# ring_modulator.net
KiCad netlist of a schematic drawn in EAGLE
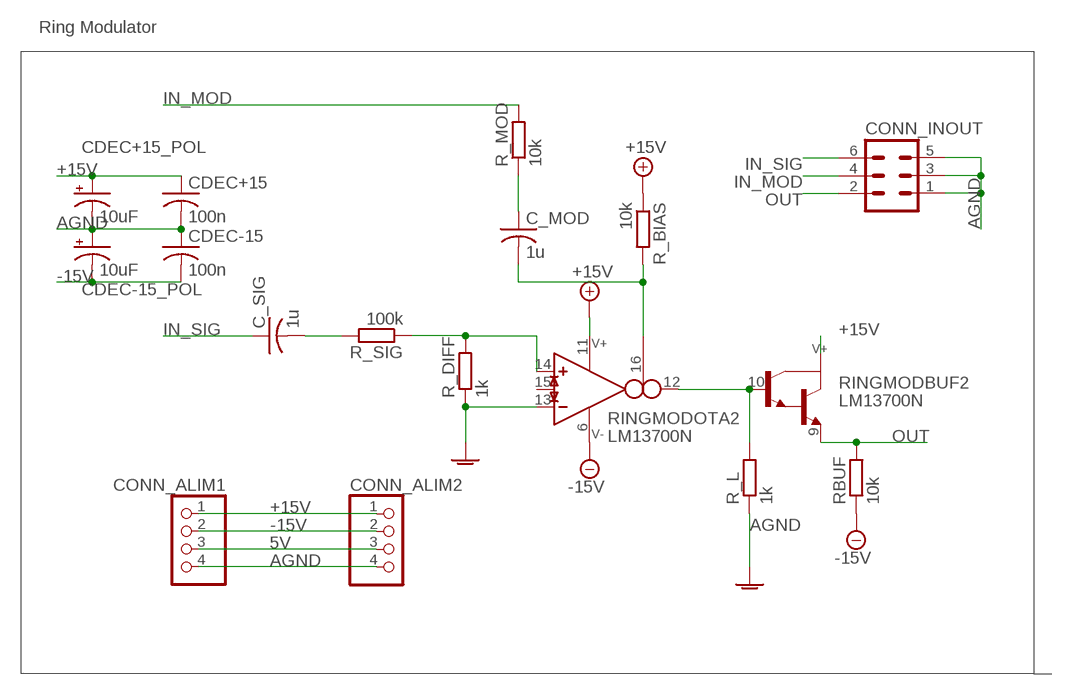
[diagram p0: schematic, sheet 1]

(export (version "E")
  (design (tool "Eeschema 10.0.6"))
  (components
    (comp (ref "CDEC+15")
      (value "100n")
      (footprint "eagle-import:C050-024X044")
      (libsource (lib "eagle-import") (part "C-US050-024X044"))
    )
    (comp (ref "CDEC+15_POL")
      (value "10uF")
      (footprint "eagle-import:CPOL-RADIAL-2.5MM-5MM-KIT")
      (libsource (lib "eagle-import") (part "10UF-POLAR-RADIAL-2.5MM-KIT-25V-20%"))
    )
    (comp (ref "CDEC-15")
      (value "100n")
      (footprint "eagle-import:C050-024X044")
      (libsource (lib "eagle-import") (part "C-US050-024X044"))
    )
    (comp (ref "CDEC-15_POL")
      (value "10uF")
      (footprint "eagle-import:CPOL-RADIAL-2.5MM-5MM-KIT")
      (libsource (lib "eagle-import") (part "10UF-POLAR-RADIAL-2.5MM-KIT-25V-20%"))
    )
    (comp (ref "CONN_ALIM1")
      (value "PINHD-1X4")
      (footprint "eagle-import:1X04")
      (libsource (lib "eagle-import") (part "PINHD-1X4"))
    )
    (comp (ref "CONN_ALIM2")
      (value "PINHD-1X4")
      (footprint "eagle-import:1X04")
      (libsource (lib "eagle-import") (part "PINHD-1X4"))
    )
    (comp (ref "CONN_INOUT")
      (value "MA03-2")
      (footprint "eagle-import:MA03-2")
      (libsource (lib "eagle-import") (part "MA03-2"))
    )
    (comp (ref "C_MOD")
      (value "1u")
      (footprint "eagle-import:C050-024X044")
      (libsource (lib "eagle-import") (part "C-US050-024X044"))
    )
    (comp (ref "C_SIG")
      (value "1u")
      (footprint "eagle-import:C050-024X044")
      (libsource (lib "eagle-import") (part "C-US050-024X044"))
    )
    (comp (ref "RBUF")
      (value "10k")
      (footprint "eagle-import:0204_7")
      (libsource (lib "eagle-import") (part "R-EU_0204/7"))
    )
    (comp (ref "RINGMOD")
      (value "LM13700N")
      (footprint "eagle-import:DIL16")
      (libsource (lib "eagle-import") (part "LM13700N"))
    )
    (comp (ref "R_BIAS")
      (value "10k")
      (footprint "eagle-import:0204_7")
      (libsource (lib "eagle-import") (part "R-EU_0204/7"))
    )
    (comp (ref "R_DIFF")
      (value "1k")
      (footprint "eagle-import:0204_7")
      (libsource (lib "eagle-import") (part "R-EU_0204/7"))
    )
    (comp (ref "R_L")
      (value "1k")
      (footprint "eagle-import:0204_7")
      (libsource (lib "eagle-import") (part "R-EU_0204/7"))
    )
    (comp (ref "R_MOD")
      (value "10k")
      (footprint "eagle-import:0204_7")
      (libsource (lib "eagle-import") (part "R-EU_0204/7"))
    )
    (comp (ref "R_SIG")
      (value "100k")
      (footprint "eagle-import:0204_7")
      (libsource (lib "eagle-import") (part "R-EU_0204/7"))
    )
  )
  (nets
    (net (code "1") (name "+15V") (class "Default")
      (node (ref "CDEC+15") (pin "1") (pinfunction "1_1") (pintype "passive"))
      (node (ref "CDEC+15_POL") (pin "1") (pinfunction "+_1") (pintype "passive"))
      (node (ref "CONN_ALIM1") (pin "1") (pinfunction "1_1") (pintype "passive"))
      (node (ref "CONN_ALIM2") (pin "1") (pinfunction "1_1") (pintype "passive"))
      (node (ref "RINGMOD") (pin "11") (pinfunction "V+_11") (pintype "power_in"))
      (node (ref "R_BIAS") (pin "1") (pinfunction "1_1") (pintype "passive"))
    )
    (net (code "2") (name "-15V") (class "Default")
      (node (ref "CDEC-15") (pin "2") (pinfunction "2_2") (pintype "passive"))
      (node (ref "CDEC-15_POL") (pin "2") (pinfunction "-_2") (pintype "passive"))
      (node (ref "CONN_ALIM1") (pin "2") (pinfunction "2_2") (pintype "passive"))
      (node (ref "CONN_ALIM2") (pin "2") (pinfunction "2_2") (pintype "passive"))
      (node (ref "RBUF") (pin "1") (pinfunction "1_1") (pintype "passive"))
      (node (ref "RINGMOD") (pin "6") (pinfunction "V-_6") (pintype "power_in"))
    )
    (net (code "3") (name "/5V") (class "Default")
      (node (ref "CONN_ALIM1") (pin "3") (pinfunction "3_3") (pintype "passive"))
      (node (ref "CONN_ALIM2") (pin "3") (pinfunction "3_3") (pintype "passive"))
    )
    (net (code "4") (name "/IN_MOD") (class "Default")
      (node (ref "CONN_INOUT") (pin "4") (pinfunction "4_4") (pintype "passive"))
      (node (ref "R_MOD") (pin "2") (pinfunction "2_2") (pintype "passive"))
    )
    (net (code "5") (name "/IN_SIG") (class "Default")
      (node (ref "CONN_INOUT") (pin "6") (pinfunction "6_6") (pintype "passive"))
      (node (ref "C_SIG") (pin "1") (pinfunction "1_1") (pintype "passive"))
    )
    (net (code "6") (name "/OUT") (class "Default")
      (node (ref "CONN_INOUT") (pin "2") (pinfunction "2_2") (pintype "passive"))
      (node (ref "RBUF") (pin "2") (pinfunction "2_2") (pintype "passive"))
      (node (ref "RINGMOD") (pin "9") (pinfunction "E_9") (pintype "passive"))
    )
    (net (code "7") (name "AGND") (class "Default")
      (node (ref "CDEC+15") (pin "2") (pinfunction "2_2") (pintype "passive"))
      (node (ref "CDEC+15_POL") (pin "2") (pinfunction "-_2") (pintype "passive"))
      (node (ref "CDEC-15") (pin "1") (pinfunction "1_1") (pintype "passive"))
      (node (ref "CDEC-15_POL") (pin "1") (pinfunction "+_1") (pintype "passive"))
      (node (ref "CONN_ALIM1") (pin "4") (pinfunction "4_4") (pintype "passive"))
      (node (ref "CONN_ALIM2") (pin "4") (pinfunction "4_4") (pintype "passive"))
      (node (ref "CONN_INOUT") (pin "1") (pinfunction "1_1") (pintype "passive"))
      (node (ref "CONN_INOUT") (pin "3") (pinfunction "3_3") (pintype "passive"))
      (node (ref "CONN_INOUT") (pin "5") (pinfunction "5_5") (pintype "passive"))
      (node (ref "RINGMOD") (pin "13") (pinfunction "IN_N_13") (pintype "input"))
      (node (ref "R_DIFF") (pin "1") (pinfunction "1_1") (pintype "passive"))
      (node (ref "R_L") (pin "1") (pinfunction "1_1") (pintype "passive"))
    )
    (net (code "8") (name "Net-(C_MOD-Pad1)") (class "Default")
      (node (ref "C_MOD") (pin "1") (pinfunction "1_1") (pintype "passive"))
      (node (ref "R_MOD") (pin "1") (pinfunction "1_1") (pintype "passive"))
    )
    (net (code "9") (name "Net-(C_SIG-Pad2)") (class "Default")
      (node (ref "C_SIG") (pin "2") (pinfunction "2_2") (pintype "passive"))
      (node (ref "R_SIG") (pin "2") (pinfunction "2_2") (pintype "passive"))
    )
    (net (code "10") (name "Net-(RINGMODB-B)") (class "Default")
      (node (ref "RINGMOD") (pin "10") (pinfunction "B_10") (pintype "passive"))
      (node (ref "RINGMOD") (pin "12") (pinfunction "OUT_12") (pintype "output"))
      (node (ref "R_L") (pin "2") (pinfunction "2_2") (pintype "passive"))
    )
    (net (code "11") (name "Net-(RINGMODD-IN_P)") (class "Default")
      (node (ref "RINGMOD") (pin "14") (pinfunction "IN_P_14") (pintype "input"))
      (node (ref "R_DIFF") (pin "2") (pinfunction "2_2") (pintype "passive"))
      (node (ref "R_SIG") (pin "1") (pinfunction "1_1") (pintype "passive"))
    )
    (net (code "12") (name "Net-(RINGMODD-I_BIAS)") (class "Default")
      (node (ref "C_MOD") (pin "2") (pinfunction "2_2") (pintype "passive"))
      (node (ref "RINGMOD") (pin "16") (pinfunction "I_BIAS_16") (pintype "input"))
      (node (ref "R_BIAS") (pin "2") (pinfunction "2_2") (pintype "passive"))
    )
    (net (code "13") (name "unconnected-(RINGMODD-I_DIODE-Pad15)") (class "Default")
      (node (ref "RINGMOD") (pin "15") (pinfunction "I_DIODE_15") (pintype "input"))
    )
  )
)
